# v6_config_io_16_17_21_22.net
KiCad netlist of a schematic drawn in Altium Designer
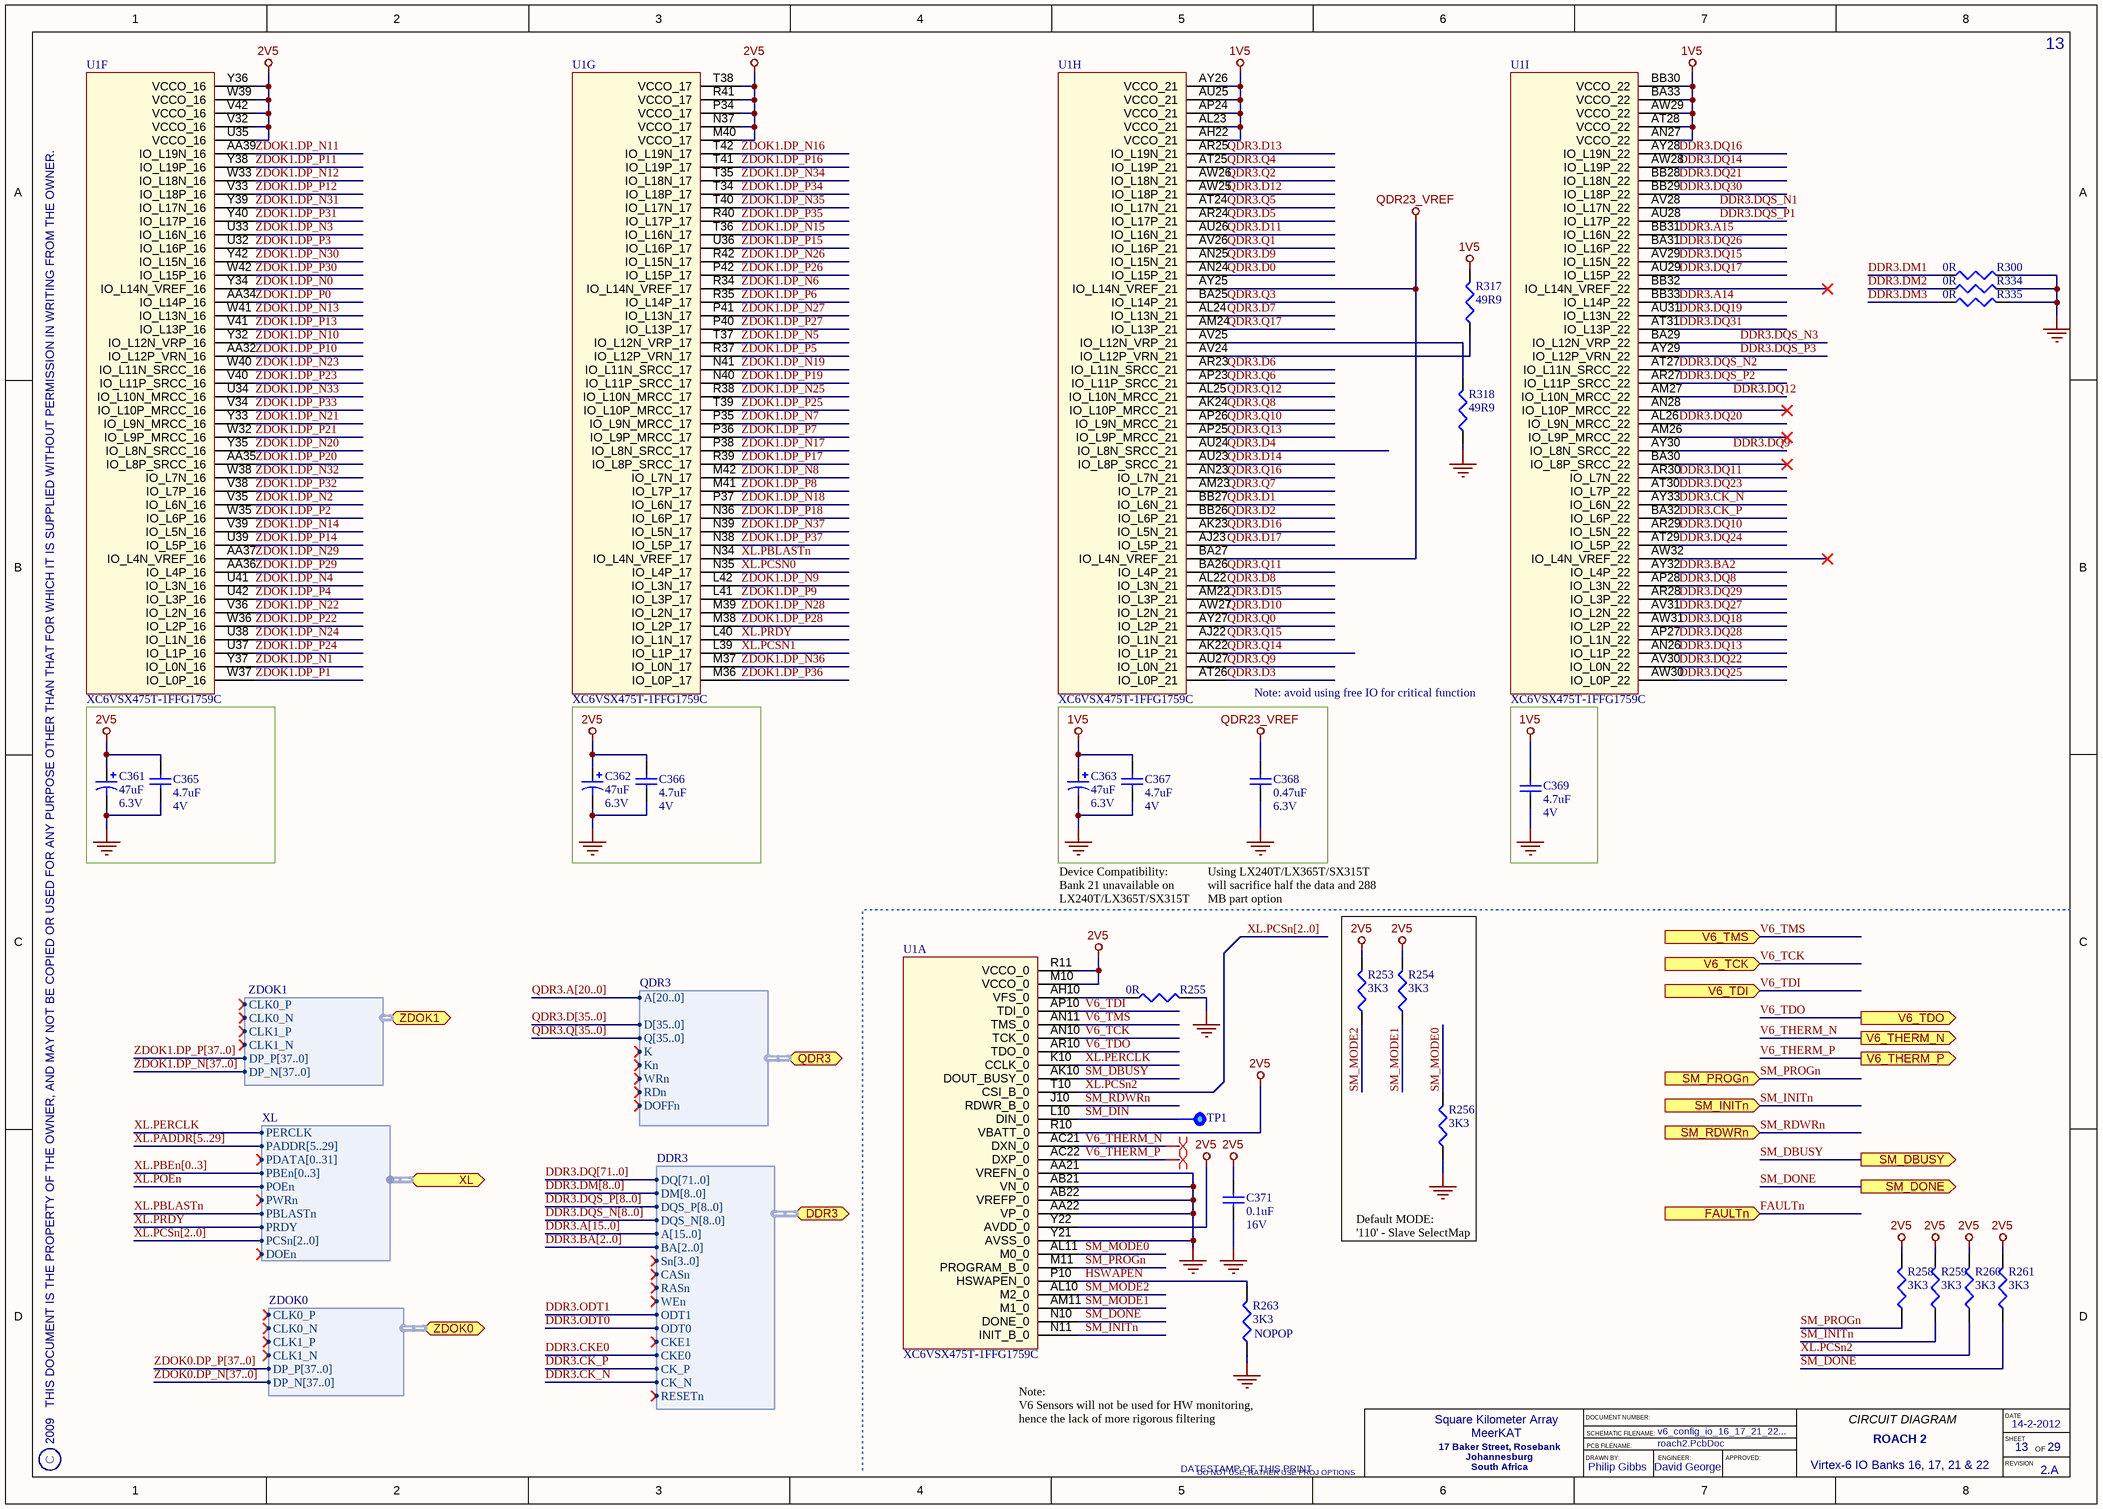
[diagram p0: v6_config_io_16_17_21_22.SchDoc]

(export (version "E")
  (design (tool "Eeschema 10.0.6"))
  (components
    (comp (ref "C361")
      (value "47uF")
      (footprint "CAPMP3528X120L")
      (description "47uF, Conductive Polymer Chip Capacitor")
      (fields
        (field (name "RATING") "6.3V")
        (field (name "MANUFACTURER") "KEMET")
        (field (name "PARTNUM") "T520T476M006ATE070")
      )
      (libsource (lib "altium_db") (part "CapPol"))
    )
    (comp (ref "C362")
      (value "47uF")
      (footprint "CAPMP3528X120L")
      (description "47uF, Conductive Polymer Chip Capacitor")
      (fields
        (field (name "RATING") "6.3V")
        (field (name "MANUFACTURER") "KEMET")
        (field (name "PARTNUM") "T520T476M006ATE070")
      )
      (libsource (lib "altium_db") (part "CapPol"))
    )
    (comp (ref "C363")
      (value "47uF")
      (footprint "CAPMP3528X120L")
      (description "47uF, Conductive Polymer Chip Capacitor")
      (fields
        (field (name "RATING") "6.3V")
        (field (name "MANUFACTURER") "KEMET")
        (field (name "PARTNUM") "T520T476M006ATE070")
      )
      (libsource (lib "altium_db") (part "CapPol"))
    )
    (comp (ref "C365")
      (value "4.7uF")
      (footprint "CAPC1005X60L")
      (description "4.7uF, Ceramic Capacitor")
      (fields
        (field (name "RATING") "4V")
        (field (name "MANUFACTURER") "MURATA")
        (field (name "PARTNUM") "AMK105BJ475MV-F")
      )
      (libsource (lib "altium_db") (part "CapStd"))
    )
    (comp (ref "C366")
      (value "4.7uF")
      (footprint "CAPC1005X60L")
      (description "4.7uF, Ceramic Capacitor")
      (fields
        (field (name "RATING") "4V")
        (field (name "MANUFACTURER") "MURATA")
        (field (name "PARTNUM") "AMK105BJ475MV-F")
      )
      (libsource (lib "altium_db") (part "CapStd"))
    )
    (comp (ref "C367")
      (value "4.7uF")
      (footprint "CAPC1005X60L")
      (description "4.7uF, Ceramic Capacitor")
      (fields
        (field (name "RATING") "4V")
        (field (name "MANUFACTURER") "MURATA")
        (field (name "PARTNUM") "AMK105BJ475MV-F")
      )
      (libsource (lib "altium_db") (part "CapStd"))
    )
    (comp (ref "C368")
      (value "0.47uF")
      (footprint "CAPC1005X55L")
      (description "0.47uF, Ceramic Capacitor")
      (fields
        (field (name "RATING") "6.3V")
        (field (name "MANUFACTURER") "MURATA")
        (field (name "PARTNUM") "GRM155R60J474KE19")
      )
      (libsource (lib "altium_db") (part "CapStd"))
    )
    (comp (ref "C369")
      (value "4.7uF")
      (footprint "CAPC1005X60L")
      (description "4.7uF, Ceramic Capacitor")
      (fields
        (field (name "RATING") "4V")
        (field (name "MANUFACTURER") "MURATA")
        (field (name "PARTNUM") "AMK105BJ475MV-F")
      )
      (libsource (lib "altium_db") (part "CapStd"))
    )
    (comp (ref "C371")
      (value "0.1uF")
      (footprint "CAPC1005X60L")
      (description "0.1uF, Ceramic Capacitor")
      (fields
        (field (name "RATING") "16V")
        (field (name "MANUFACTURER") "VENKEL")
        (field (name "PARTNUM") "C0402X7R160-104KN")
      )
      (libsource (lib "altium_db") (part "CapStd"))
    )
    (comp (ref "R253")
      (value "3K3")
      (footprint "RESC1005X40L")
      (description "3K3, 1.1mm x 0.5mm, Thick Film Resistor")
      (fields (field (name "MANUFACTURER") "ROYALOHM") (field (name "PARTNUM") "0402WGJ0332T1E"))
      (libsource (lib "altium_db") (part "ResStd"))
    )
    (comp (ref "R254")
      (value "3K3")
      (footprint "RESC1005X40L")
      (description "3K3, 1.1mm x 0.5mm, Thick Film Resistor")
      (fields (field (name "MANUFACTURER") "ROYALOHM") (field (name "PARTNUM") "0402WGJ0332T1E"))
      (libsource (lib "altium_db") (part "ResStd"))
    )
    (comp (ref "R255")
      (value "0R")
      (footprint "RESC1005X40L")
      (description "0R, 1.1mm x 0.5mm, Thick Film Resistor")
      (fields (field (name "MANUFACTURER") "ROYALOHM") (field (name "PARTNUM") "0402WG00000T1E"))
      (libsource (lib "altium_db") (part "ResStd"))
    )
    (comp (ref "R256")
      (value "3K3")
      (footprint "RESC1005X40L")
      (description "3K3, 1.1mm x 0.5mm, Thick Film Resistor")
      (fields (field (name "MANUFACTURER") "ROYALOHM") (field (name "PARTNUM") "0402WGJ0332T1E"))
      (libsource (lib "altium_db") (part "ResStd"))
    )
    (comp (ref "R258")
      (value "3K3")
      (footprint "RESC1005X40L")
      (description "3K3, 1.1mm x 0.5mm, Thick Film Resistor")
      (fields (field (name "MANUFACTURER") "ROYALOHM") (field (name "PARTNUM") "0402WGJ0332T1E"))
      (libsource (lib "altium_db") (part "ResStd"))
    )
    (comp (ref "R259")
      (value "3K3")
      (footprint "RESC1005X40L")
      (description "3K3, 1.1mm x 0.5mm, Thick Film Resistor")
      (fields (field (name "MANUFACTURER") "ROYALOHM") (field (name "PARTNUM") "0402WGJ0332T1E"))
      (libsource (lib "altium_db") (part "ResStd"))
    )
    (comp (ref "R260")
      (value "3K3")
      (footprint "RESC1005X40L")
      (description "3K3, 1.1mm x 0.5mm, Thick Film Resistor")
      (fields (field (name "MANUFACTURER") "ROYALOHM") (field (name "PARTNUM") "0402WGJ0332T1E"))
      (libsource (lib "altium_db") (part "ResStd"))
    )
    (comp (ref "R261")
      (value "3K3")
      (footprint "RESC1005X40L")
      (description "3K3, 1.1mm x 0.5mm, Thick Film Resistor")
      (fields (field (name "MANUFACTURER") "ROYALOHM") (field (name "PARTNUM") "0402WGJ0332T1E"))
      (libsource (lib "altium_db") (part "ResStd"))
    )
    (comp (ref "R263")
      (value "3K3")
      (footprint "RESC1005X40L")
      (description "3K3, 1.1mm x 0.5mm, Thick Film Resistor")
      (fields (field (name "MANUFACTURER") "ROYALOHM") (field (name "PARTNUM") "0402WGJ0332T1E"))
      (libsource (lib "altium_db") (part "ResStd"))
    )
    (comp (ref "R300")
      (value "0R")
      (footprint "RESC1005X40L")
      (description "0R, 1.1mm x 0.5mm, Thick Film Resistor")
      (fields (field (name "MANUFACTURER") "ROYALOHM") (field (name "PARTNUM") "0402WG00000T1E"))
      (libsource (lib "altium_db") (part "ResStd"))
    )
    (comp (ref "R317")
      (value "49R9")
      (footprint "RESC1005X40L")
      (description "49R9, 1.1mm x 0.5mm, Thick Film Resistor")
      (fields (field (name "MANUFACTURER") "ROYALOHM") (field (name "PARTNUM") "0402WGF499JT1E"))
      (libsource (lib "altium_db") (part "ResStd"))
    )
    (comp (ref "R318")
      (value "49R9")
      (footprint "RESC1005X40L")
      (description "49R9, 1.1mm x 0.5mm, Thick Film Resistor")
      (fields (field (name "MANUFACTURER") "ROYALOHM") (field (name "PARTNUM") "0402WGF499JT1E"))
      (libsource (lib "altium_db") (part "ResStd"))
    )
    (comp (ref "R334")
      (value "0R")
      (footprint "RESC1005X40L")
      (description "0R, 1.1mm x 0.5mm, Thick Film Resistor")
      (fields (field (name "MANUFACTURER") "ROYALOHM") (field (name "PARTNUM") "0402WG00000T1E"))
      (libsource (lib "altium_db") (part "ResStd"))
    )
    (comp (ref "R335")
      (value "0R")
      (footprint "RESC1005X40L")
      (description "0R, 1.1mm x 0.5mm, Thick Film Resistor")
      (fields (field (name "MANUFACTURER") "ROYALOHM") (field (name "PARTNUM") "0402WG00000T1E"))
      (libsource (lib "altium_db") (part "ResStd"))
    )
    (comp (ref "TP1")
      (value "Testpoint")
      (footprint "TP100")
      (description "1mm Diameter, through-hole, Circular Test-point")
      (libsource (lib "altium_db") (part "Testpoint"))
    )
    (comp (ref "U1")
      (value "XC6VSX475T-1FFG1759C")
      (footprint "FFG1759")
      (description "Virtex-6 475SXT 1760-pin FPGA")
      (fields (field (name "MANUFACTURER") "Xilinx"))
      (libsource (lib "altium_db") (part "XC6VSX475T-1FFG1759C"))
    )
  )
  (nets
    (net (code "161") (name "/DDR3.A14") (class "Default")
      (node (ref "U1") (pin "BB33") (pinfunction "IO_L14P_22_BB33") (pintype "passive"))
    )
    (net (code "162") (name "/DDR3.A15") (class "Default")
      (node (ref "U1") (pin "BB31") (pinfunction "IO_L16N_22_BB31") (pintype "passive"))
    )
    (net (code "164") (name "/DDR3.BA2") (class "Default")
      (node (ref "U1") (pin "AY32") (pinfunction "IO_L4P_22_AY32") (pintype "passive"))
    )
    (net (code "167") (name "/DDR3.CK_N") (class "Default")
      (node (ref "U1") (pin "AY33") (pinfunction "IO_L6N_22_AY33") (pintype "passive"))
    )
    (net (code "168") (name "/DDR3.CK_P") (class "Default")
      (node (ref "U1") (pin "BA32") (pinfunction "IO_L6P_22_BA32") (pintype "passive"))
    )
    (net (code "169") (name "/DDR3.DM1") (class "Default")
      (node (ref "R300") (pin "1") (pinfunction "1_1") (pintype "passive"))
    )
    (net (code "170") (name "/DDR3.DM2") (class "Default")
      (node (ref "R334") (pin "1") (pinfunction "1_1") (pintype "passive"))
    )
    (net (code "171") (name "/DDR3.DM3") (class "Default")
      (node (ref "R335") (pin "1") (pinfunction "1_1") (pintype "passive"))
    )
    (net (code "173") (name "/DDR3.DQ8") (class "Default")
      (node (ref "U1") (pin "AP28") (pinfunction "IO_L3N_22_AP28") (pintype "passive"))
    )
    (net (code "174") (name "/DDR3.DQ9") (class "Default")
      (node (ref "U1") (pin "AY30") (pinfunction "IO_L8N_SRCC_22_AY30") (pintype "passive"))
    )
    (net (code "175") (name "/DDR3.DQ10") (class "Default")
      (node (ref "U1") (pin "AR29") (pinfunction "IO_L5N_22_AR29") (pintype "passive"))
    )
    (net (code "176") (name "/DDR3.DQ11") (class "Default")
      (node (ref "U1") (pin "AR30") (pinfunction "IO_L7N_22_AR30") (pintype "passive"))
    )
    (net (code "177") (name "/DDR3.DQ12") (class "Default")
      (node (ref "U1") (pin "AM27") (pinfunction "IO_L10N_MRCC_22_AM27") (pintype "passive"))
    )
    (net (code "178") (name "/DDR3.DQ13") (class "Default")
      (node (ref "U1") (pin "AN26") (pinfunction "IO_L1P_22_AN26") (pintype "passive"))
    )
    (net (code "179") (name "/DDR3.DQ14") (class "Default")
      (node (ref "U1") (pin "AW28") (pinfunction "IO_L19P_22_AW28") (pintype "passive"))
    )
    (net (code "180") (name "/DDR3.DQ15") (class "Default")
      (node (ref "U1") (pin "AV29") (pinfunction "IO_L15N_22_AV29") (pintype "passive"))
    )
    (net (code "181") (name "/DDR3.DQ16") (class "Default")
      (node (ref "U1") (pin "AY28") (pinfunction "IO_L19N_22_AY28") (pintype "passive"))
    )
    (net (code "182") (name "/DDR3.DQ17") (class "Default")
      (node (ref "U1") (pin "AU29") (pinfunction "IO_L15P_22_AU29") (pintype "passive"))
    )
    (net (code "183") (name "/DDR3.DQ18") (class "Default")
      (node (ref "U1") (pin "AW31") (pinfunction "IO_L2P_22_AW31") (pintype "passive"))
    )
    (net (code "184") (name "/DDR3.DQ19") (class "Default")
      (node (ref "U1") (pin "AU31") (pinfunction "IO_L13N_22_AU31") (pintype "passive"))
    )
    (net (code "185") (name "/DDR3.DQ20") (class "Default")
      (node (ref "U1") (pin "AL26") (pinfunction "IO_L9N_MRCC_22_AL26") (pintype "passive"))
    )
    (net (code "186") (name "/DDR3.DQ21") (class "Default")
      (node (ref "U1") (pin "BB28") (pinfunction "IO_L18N_22_BB28") (pintype "passive"))
    )
    (net (code "187") (name "/DDR3.DQ22") (class "Default")
      (node (ref "U1") (pin "AV30") (pinfunction "IO_L0N_22_AV30") (pintype "passive"))
    )
    (net (code "188") (name "/DDR3.DQ23") (class "Default")
      (node (ref "U1") (pin "AT30") (pinfunction "IO_L7P_22_AT30") (pintype "passive"))
    )
    (net (code "189") (name "/DDR3.DQ24") (class "Default")
      (node (ref "U1") (pin "AT29") (pinfunction "IO_L5P_22_AT29") (pintype "passive"))
    )
    (net (code "190") (name "/DDR3.DQ25") (class "Default")
      (node (ref "U1") (pin "AW30") (pinfunction "IO_L0P_22_AW30") (pintype "passive"))
    )
    (net (code "191") (name "/DDR3.DQ26") (class "Default")
      (node (ref "U1") (pin "BA31") (pinfunction "IO_L16P_22_BA31") (pintype "passive"))
    )
    (net (code "192") (name "/DDR3.DQ27") (class "Default")
      (node (ref "U1") (pin "AV31") (pinfunction "IO_L2N_22_AV31") (pintype "passive"))
    )
    (net (code "193") (name "/DDR3.DQ28") (class "Default")
      (node (ref "U1") (pin "AP27") (pinfunction "IO_L1N_22_AP27") (pintype "passive"))
    )
    (net (code "194") (name "/DDR3.DQ29") (class "Default")
      (node (ref "U1") (pin "AR28") (pinfunction "IO_L3P_22_AR28") (pintype "passive"))
    )
    (net (code "195") (name "/DDR3.DQ30") (class "Default")
      (node (ref "U1") (pin "BB29") (pinfunction "IO_L18P_22_BB29") (pintype "passive"))
    )
    (net (code "196") (name "/DDR3.DQ31") (class "Default")
      (node (ref "U1") (pin "AT31") (pinfunction "IO_L13P_22_AT31") (pintype "passive"))
    )
    (net (code "197") (name "/DDR3.DQS_N1") (class "Default")
      (node (ref "U1") (pin "AV28") (pinfunction "IO_L17N_22_AV28") (pintype "passive"))
    )
    (net (code "198") (name "/DDR3.DQS_N2") (class "Default")
      (node (ref "U1") (pin "AT27") (pinfunction "IO_L11N_SRCC_22_AT27") (pintype "passive"))
    )
    (net (code "199") (name "/DDR3.DQS_N3") (class "Default")
      (node (ref "U1") (pin "BA29") (pinfunction "IO_L12N_VRP_22_BA29") (pintype "passive"))
    )
    (net (code "201") (name "/DDR3.DQS_P1") (class "Default")
      (node (ref "U1") (pin "AU28") (pinfunction "IO_L17P_22_AU28") (pintype "passive"))
    )
    (net (code "202") (name "/DDR3.DQS_P2") (class "Default")
      (node (ref "U1") (pin "AR27") (pinfunction "IO_L11P_SRCC_22_AR27") (pintype "passive"))
    )
    (net (code "203") (name "/DDR3.DQS_P3") (class "Default")
      (node (ref "U1") (pin "AY29") (pinfunction "IO_L12P_VRN_22_AY29") (pintype "passive"))
    )
    (net (code "209") (name "/HSWAPEN") (class "Default")
      (node (ref "R263") (pin "2") (pinfunction "2_2") (pintype "passive"))
      (node (ref "U1") (pin "P10") (pinfunction "HSWAPEN_0_P10") (pintype "passive"))
    )
    (net (code "211") (name "/QDR3.D0") (class "Default")
      (node (ref "U1") (pin "AN24") (pinfunction "IO_L15P_21_AN24") (pintype "passive"))
    )
    (net (code "212") (name "/QDR3.D1") (class "Default")
      (node (ref "U1") (pin "BB27") (pinfunction "IO_L6N_21_BB27") (pintype "passive"))
    )
    (net (code "213") (name "/QDR3.D2") (class "Default")
      (node (ref "U1") (pin "BB26") (pinfunction "IO_L6P_21_BB26") (pintype "passive"))
    )
    (net (code "214") (name "/QDR3.D3") (class "Default")
      (node (ref "U1") (pin "AT26") (pinfunction "IO_L0P_21_AT26") (pintype "passive"))
    )
    (net (code "215") (name "/QDR3.D4") (class "Default")
      (node (ref "U1") (pin "AU24") (pinfunction "IO_L8N_SRCC_21_AU24") (pintype "passive"))
    )
    (net (code "216") (name "/QDR3.D5") (class "Default")
      (node (ref "U1") (pin "AR24") (pinfunction "IO_L17P_21_AR24") (pintype "passive"))
    )
    (net (code "217") (name "/QDR3.D6") (class "Default")
      (node (ref "U1") (pin "AR23") (pinfunction "IO_L11N_SRCC_21_AR23") (pintype "passive"))
    )
    (net (code "218") (name "/QDR3.D7") (class "Default")
      (node (ref "U1") (pin "AL24") (pinfunction "IO_L13N_21_AL24") (pintype "passive"))
    )
    (net (code "219") (name "/QDR3.D8") (class "Default")
      (node (ref "U1") (pin "AL22") (pinfunction "IO_L3N_21_AL22") (pintype "passive"))
    )
    (net (code "220") (name "/QDR3.D9") (class "Default")
      (node (ref "U1") (pin "AN25") (pinfunction "IO_L15N_21_AN25") (pintype "passive"))
    )
    (net (code "221") (name "/QDR3.D10") (class "Default")
      (node (ref "U1") (pin "AW27") (pinfunction "IO_L2N_21_AW27") (pintype "passive"))
    )
    (net (code "222") (name "/QDR3.D11") (class "Default")
      (node (ref "U1") (pin "AU26") (pinfunction "IO_L16N_21_AU26") (pintype "passive"))
    )
    (net (code "223") (name "/QDR3.D12") (class "Default")
      (node (ref "U1") (pin "AW25") (pinfunction "IO_L18P_21_AW25") (pintype "passive"))
    )
    (net (code "224") (name "/QDR3.D13") (class "Default")
      (node (ref "U1") (pin "AR25") (pinfunction "IO_L19N_21_AR25") (pintype "passive"))
    )
    (net (code "225") (name "/QDR3.D14") (class "Default")
      (node (ref "U1") (pin "AU23") (pinfunction "IO_L8P_SRCC_21_AU23") (pintype "passive"))
    )
    (net (code "226") (name "/QDR3.D15") (class "Default")
      (node (ref "U1") (pin "AM22") (pinfunction "IO_L3P_21_AM22") (pintype "passive"))
    )
    (net (code "227") (name "/QDR3.D16") (class "Default")
      (node (ref "U1") (pin "AK23") (pinfunction "IO_L5N_21_AK23") (pintype "passive"))
    )
    (net (code "228") (name "/QDR3.D17") (class "Default")
      (node (ref "U1") (pin "AJ23") (pinfunction "IO_L5P_21_AJ23") (pintype "passive"))
    )
    (net (code "230") (name "/QDR3.Q0") (class "Default")
      (node (ref "U1") (pin "AY27") (pinfunction "IO_L2P_21_AY27") (pintype "passive"))
    )
    (net (code "231") (name "/QDR3.Q1") (class "Default")
      (node (ref "U1") (pin "AV26") (pinfunction "IO_L16P_21_AV26") (pintype "passive"))
    )
    (net (code "232") (name "/QDR3.Q2") (class "Default")
      (node (ref "U1") (pin "AW26") (pinfunction "IO_L18N_21_AW26") (pintype "passive"))
    )
    (net (code "233") (name "/QDR3.Q3") (class "Default")
      (node (ref "U1") (pin "BA25") (pinfunction "IO_L14P_21_BA25") (pintype "passive"))
    )
    (net (code "234") (name "/QDR3.Q4") (class "Default")
      (node (ref "U1") (pin "AT25") (pinfunction "IO_L19P_21_AT25") (pintype "passive"))
    )
    (net (code "235") (name "/QDR3.Q5") (class "Default")
      (node (ref "U1") (pin "AT24") (pinfunction "IO_L17N_21_AT24") (pintype "passive"))
    )
    (net (code "236") (name "/QDR3.Q6") (class "Default")
      (node (ref "U1") (pin "AP23") (pinfunction "IO_L11P_SRCC_21_AP23") (pintype "passive"))
    )
    (net (code "237") (name "/QDR3.Q7") (class "Default")
      (node (ref "U1") (pin "AM23") (pinfunction "IO_L7P_21_AM23") (pintype "passive"))
    )
    (net (code "238") (name "/QDR3.Q8") (class "Default")
      (node (ref "U1") (pin "AK24") (pinfunction "IO_L10P_MRCC_21_AK24") (pintype "passive"))
    )
    (net (code "239") (name "/QDR3.Q9") (class "Default")
      (node (ref "U1") (pin "AU27") (pinfunction "IO_L0N_21_AU27") (pintype "passive"))
    )
    (net (code "240") (name "/QDR3.Q10") (class "Default")
      (node (ref "U1") (pin "AP26") (pinfunction "IO_L9N_MRCC_21_AP26") (pintype "passive"))
    )
    (net (code "241") (name "/QDR3.Q11") (class "Default")
      (node (ref "U1") (pin "BA26") (pinfunction "IO_L4P_21_BA26") (pintype "passive"))
    )
    (net (code "242") (name "/QDR3.Q12") (class "Default")
      (node (ref "U1") (pin "AL25") (pinfunction "IO_L10N_MRCC_21_AL25") (pintype "passive"))
    )
    (net (code "243") (name "/QDR3.Q13") (class "Default")
      (node (ref "U1") (pin "AP25") (pinfunction "IO_L9P_MRCC_21_AP25") (pintype "passive"))
    )
    (net (code "244") (name "/QDR3.Q14") (class "Default")
      (node (ref "U1") (pin "AK22") (pinfunction "IO_L1P_21_AK22") (pintype "passive"))
    )
    (net (code "245") (name "/QDR3.Q15") (class "Default")
      (node (ref "U1") (pin "AJ22") (pinfunction "IO_L1N_21_AJ22") (pintype "passive"))
    )
    (net (code "246") (name "/QDR3.Q16") (class "Default")
      (node (ref "U1") (pin "AN23") (pinfunction "IO_L7N_21_AN23") (pintype "passive"))
    )
    (net (code "247") (name "/QDR3.Q17") (class "Default")
      (node (ref "U1") (pin "AM24") (pinfunction "IO_L13P_21_AM24") (pintype "passive"))
    )
    (net (code "249") (name "/SM_DBUSY") (class "Default")
      (node (ref "U1") (pin "AK10") (pinfunction "DOUT_BUSY_0_AK10") (pintype "passive"))
    )
    (net (code "250") (name "/SM_DIN") (class "Default")
      (node (ref "TP1") (pin "1") (pinfunction "1_1") (pintype "passive"))
      (node (ref "U1") (pin "L10") (pinfunction "DIN_0_L10") (pintype "passive"))
    )
    (net (code "251") (name "/SM_DONE") (class "Default")
      (node (ref "R261") (pin "1") (pinfunction "1_1") (pintype "passive"))
      (node (ref "U1") (pin "N10") (pinfunction "DONE_0_N10") (pintype "passive"))
    )
    (net (code "252") (name "/SM_INITn") (class "Default")
      (node (ref "R259") (pin "1") (pinfunction "1_1") (pintype "passive"))
      (node (ref "U1") (pin "N11") (pinfunction "INIT_B_0_N11") (pintype "passive"))
    )
    (net (code "253") (name "/SM_MODE0") (class "Default")
      (node (ref "R256") (pin "2") (pinfunction "2_2") (pintype "passive"))
      (node (ref "U1") (pin "AL11") (pinfunction "M0_0_AL11") (pintype "passive"))
    )
    (net (code "254") (name "/SM_MODE1") (class "Default")
      (node (ref "R254") (pin "1") (pinfunction "1_1") (pintype "passive"))
      (node (ref "U1") (pin "AM11") (pinfunction "M1_0_AM11") (pintype "passive"))
    )
    (net (code "255") (name "/SM_MODE2") (class "Default")
      (node (ref "R253") (pin "1") (pinfunction "1_1") (pintype "passive"))
      (node (ref "U1") (pin "AL10") (pinfunction "M2_0_AL10") (pintype "passive"))
    )
    (net (code "256") (name "/SM_PROGn") (class "Default")
      (node (ref "R258") (pin "1") (pinfunction "1_1") (pintype "passive"))
      (node (ref "U1") (pin "M11") (pinfunction "PROGRAM_B_0_M11") (pintype "passive"))
    )
    (net (code "257") (name "/SM_RDWRn") (class "Default")
      (node (ref "U1") (pin "J10") (pinfunction "RDWR_B_0_J10") (pintype "passive"))
    )
    (net (code "258") (name "/V6_TCK") (class "Default")
      (node (ref "U1") (pin "AN10") (pinfunction "TCK_0_AN10") (pintype "passive"))
    )
    (net (code "259") (name "/V6_TDI") (class "Default")
      (node (ref "U1") (pin "AP10") (pinfunction "TDI_0_AP10") (pintype "passive"))
    )
    (net (code "260") (name "/V6_TDO") (class "Default")
      (node (ref "U1") (pin "AR10") (pinfunction "TDO_0_AR10") (pintype "passive"))
    )
    (net (code "261") (name "/V6_THERM_N") (class "Default")
      (node (ref "U1") (pin "AC21") (pinfunction "DXN_0_AC21") (pintype "passive"))
    )
    (net (code "262") (name "/V6_THERM_P") (class "Default")
      (node (ref "U1") (pin "AC22") (pinfunction "DXP_0_AC22") (pintype "passive"))
    )
    (net (code "263") (name "/V6_TMS") (class "Default")
      (node (ref "U1") (pin "AN11") (pinfunction "TMS_0_AN11") (pintype "passive"))
    )
    (net (code "265") (name "/XL.PBLASTn") (class "Default")
      (node (ref "U1") (pin "N34") (pinfunction "IO_L4N_VREF_17_N34") (pintype "passive"))
    )
    (net (code "266") (name "/XL.PCSN0") (class "Default")
      (node (ref "U1") (pin "N35") (pinfunction "IO_L4P_17_N35") (pintype "passive"))
    )
    (net (code "267") (name "/XL.PCSN1") (class "Default")
      (node (ref "U1") (pin "L39") (pinfunction "IO_L1P_17_L39") (pintype "passive"))
    )
    (net (code "268") (name "/XL.PCSn2") (class "Default")
      (node (ref "R260") (pin "1") (pinfunction "1_1") (pintype "passive"))
      (node (ref "U1") (pin "T10") (pinfunction "CSI_B_0_T10") (pintype "passive"))
    )
    (net (code "270") (name "/XL.PERCLK") (class "Default")
      (node (ref "U1") (pin "K10") (pinfunction "CCLK_0_K10") (pintype "passive"))
    )
    (net (code "272") (name "/XL.PRDY") (class "Default")
      (node (ref "U1") (pin "L40") (pinfunction "IO_L1N_17_L40") (pintype "passive"))
    )
    (net (code "276") (name "/ZDOK1.DP_N0") (class "Default")
      (node (ref "U1") (pin "Y34") (pinfunction "IO_L14N_VREF_16_Y34") (pintype "passive"))
    )
    (net (code "277") (name "/ZDOK1.DP_N1") (class "Default")
      (node (ref "U1") (pin "Y37") (pinfunction "IO_L0N_16_Y37") (pintype "passive"))
    )
    (net (code "278") (name "/ZDOK1.DP_N2") (class "Default")
      (node (ref "U1") (pin "V35") (pinfunction "IO_L6N_16_V35") (pintype "passive"))
    )
    (net (code "279") (name "/ZDOK1.DP_N3") (class "Default")
      (node (ref "U1") (pin "U33") (pinfunction "IO_L16N_16_U33") (pintype "passive"))
    )
    (net (code "280") (name "/ZDOK1.DP_N4") (class "Default")
      (node (ref "U1") (pin "U41") (pinfunction "IO_L3N_16_U41") (pintype "passive"))
    )
    (net (code "281") (name "/ZDOK1.DP_N5") (class "Default")
      (node (ref "U1") (pin "T37") (pinfunction "IO_L12N_VRP_17_T37") (pintype "passive"))
    )
    (net (code "282") (name "/ZDOK1.DP_N6") (class "Default")
      (node (ref "U1") (pin "R34") (pinfunction "IO_L14N_VREF_17_R34") (pintype "passive"))
    )
    (net (code "283") (name "/ZDOK1.DP_N7") (class "Default")
      (node (ref "U1") (pin "P35") (pinfunction "IO_L9N_MRCC_17_P35") (pintype "passive"))
    )
    (net (code "284") (name "/ZDOK1.DP_N8") (class "Default")
      (node (ref "U1") (pin "M42") (pinfunction "IO_L7N_17_M42") (pintype "passive"))
    )
    (net (code "285") (name "/ZDOK1.DP_N9") (class "Default")
      (node (ref "U1") (pin "L42") (pinfunction "IO_L3N_17_L42") (pintype "passive"))
    )
    (net (code "286") (name "/ZDOK1.DP_N10") (class "Default")
      (node (ref "U1") (pin "Y32") (pinfunction "IO_L12N_VRP_16_Y32") (pintype "passive"))
    )
    (net (code "287") (name "/ZDOK1.DP_N11") (class "Default")
      (node (ref "U1") (pin "AA39") (pinfunction "IO_L19N_16_AA39") (pintype "passive"))
    )
    (net (code "288") (name "/ZDOK1.DP_N12") (class "Default")
      (node (ref "U1") (pin "W33") (pinfunction "IO_L18N_16_W33") (pintype "passive"))
    )
    (net (code "289") (name "/ZDOK1.DP_N13") (class "Default")
      (node (ref "U1") (pin "W41") (pinfunction "IO_L13N_16_W41") (pintype "passive"))
    )
    (net (code "290") (name "/ZDOK1.DP_N14") (class "Default")
      (node (ref "U1") (pin "V39") (pinfunction "IO_L5N_16_V39") (pintype "passive"))
    )
    (net (code "291") (name "/ZDOK1.DP_N15") (class "Default")
      (node (ref "U1") (pin "T36") (pinfunction "IO_L16N_17_T36") (pintype "passive"))
    )
    (net (code "292") (name "/ZDOK1.DP_N16") (class "Default")
      (node (ref "U1") (pin "T42") (pinfunction "IO_L19N_17_T42") (pintype "passive"))
    )
    (net (code "293") (name "/ZDOK1.DP_N17") (class "Default")
      (node (ref "U1") (pin "P38") (pinfunction "IO_L8N_SRCC_17_P38") (pintype "passive"))
    )
    (net (code "294") (name "/ZDOK1.DP_N18") (class "Default")
      (node (ref "U1") (pin "P37") (pinfunction "IO_L6N_17_P37") (pintype "passive"))
    )
    (net (code "295") (name "/ZDOK1.DP_N19") (class "Default")
      (node (ref "U1") (pin "N41") (pinfunction "IO_L11N_SRCC_17_N41") (pintype "passive"))
    )
    (net (code "296") (name "/ZDOK1.DP_N20") (class "Default")
      (node (ref "U1") (pin "Y35") (pinfunction "IO_L8N_SRCC_16_Y35") (pintype "passive"))
    )
    (net (code "297") (name "/ZDOK1.DP_N21") (class "Default")
      (node (ref "U1") (pin "Y33") (pinfunction "IO_L9N_MRCC_16_Y33") (pintype "passive"))
    )
    (net (code "298") (name "/ZDOK1.DP_N22") (class "Default")
      (node (ref "U1") (pin "V36") (pinfunction "IO_L2N_16_V36") (pintype "passive"))
    )
    (net (code "299") (name "/ZDOK1.DP_N23") (class "Default")
      (node (ref "U1") (pin "W40") (pinfunction "IO_L11N_SRCC_16_W40") (pintype "passive"))
    )
    (net (code "300") (name "/ZDOK1.DP_N24") (class "Default")
      (node (ref "U1") (pin "U38") (pinfunction "IO_L1N_16_U38") (pintype "passive"))
    )
    (net (code "301") (name "/ZDOK1.DP_N25") (class "Default")
      (node (ref "U1") (pin "R38") (pinfunction "IO_L10N_MRCC_17_R38") (pintype "passive"))
    )
    (net (code "302") (name "/ZDOK1.DP_N26") (class "Default")
      (node (ref "U1") (pin "R42") (pinfunction "IO_L15N_17_R42") (pintype "passive"))
    )
    (net (code "303") (name "/ZDOK1.DP_N27") (class "Default")
      (node (ref "U1") (pin "P41") (pinfunction "IO_L13N_17_P41") (pintype "passive"))
    )
    (net (code "304") (name "/ZDOK1.DP_N28") (class "Default")
      (node (ref "U1") (pin "M39") (pinfunction "IO_L2N_17_M39") (pintype "passive"))
    )
    (net (code "305") (name "/ZDOK1.DP_N29") (class "Default")
      (node (ref "U1") (pin "AA37") (pinfunction "IO_L4N_VREF_16_AA37") (pintype "passive"))
    )
    (net (code "306") (name "/ZDOK1.DP_N30") (class "Default")
      (node (ref "U1") (pin "Y42") (pinfunction "IO_L15N_16_Y42") (pintype "passive"))
    )
    (net (code "307") (name "/ZDOK1.DP_N31") (class "Default")
      (node (ref "U1") (pin "Y39") (pinfunction "IO_L17N_16_Y39") (pintype "passive"))
    )
    (net (code "308") (name "/ZDOK1.DP_N32") (class "Default")
      (node (ref "U1") (pin "W38") (pinfunction "IO_L7N_16_W38") (pintype "passive"))
    )
    (net (code "309") (name "/ZDOK1.DP_N33") (class "Default")
      (node (ref "U1") (pin "U34") (pinfunction "IO_L10N_MRCC_16_U34") (pintype "passive"))
    )
    (net (code "310") (name "/ZDOK1.DP_N34") (class "Default")
      (node (ref "U1") (pin "T35") (pinfunction "IO_L18N_17_T35") (pintype "passive"))
    )
    (net (code "311") (name "/ZDOK1.DP_N35") (class "Default")
      (node (ref "U1") (pin "T40") (pinfunction "IO_L17N_17_T40") (pintype "passive"))
    )
    (net (code "312") (name "/ZDOK1.DP_N36") (class "Default")
      (node (ref "U1") (pin "M37") (pinfunction "IO_L0N_17_M37") (pintype "passive"))
    )
    (net (code "313") (name "/ZDOK1.DP_N37") (class "Default")
      (node (ref "U1") (pin "N39") (pinfunction "IO_L5N_17_N39") (pintype "passive"))
    )
    (net (code "314") (name "/ZDOK1.DP_P0") (class "Default")
      (node (ref "U1") (pin "AA34") (pinfunction "IO_L14P_16_AA34") (pintype "passive"))
    )
    (net (code "315") (name "/ZDOK1.DP_P1") (class "Default")
      (node (ref "U1") (pin "W37") (pinfunction "IO_L0P_16_W37") (pintype "passive"))
    )
    (net (code "316") (name "/ZDOK1.DP_P2") (class "Default")
      (node (ref "U1") (pin "W35") (pinfunction "IO_L6P_16_W35") (pintype "passive"))
    )
    (net (code "317") (name "/ZDOK1.DP_P3") (class "Default")
      (node (ref "U1") (pin "U32") (pinfunction "IO_L16P_16_U32") (pintype "passive"))
    )
    (net (code "318") (name "/ZDOK1.DP_P4") (class "Default")
      (node (ref "U1") (pin "U42") (pinfunction "IO_L3P_16_U42") (pintype "passive"))
    )
    (net (code "319") (name "/ZDOK1.DP_P5") (class "Default")
      (node (ref "U1") (pin "R37") (pinfunction "IO_L12P_VRN_17_R37") (pintype "passive"))
    )
    (net (code "320") (name "/ZDOK1.DP_P6") (class "Default")
      (node (ref "U1") (pin "R35") (pinfunction "IO_L14P_17_R35") (pintype "passive"))
    )
    (net (code "321") (name "/ZDOK1.DP_P7") (class "Default")
      (node (ref "U1") (pin "P36") (pinfunction "IO_L9P_MRCC_17_P36") (pintype "passive"))
    )
    (net (code "322") (name "/ZDOK1.DP_P8") (class "Default")
      (node (ref "U1") (pin "M41") (pinfunction "IO_L7P_17_M41") (pintype "passive"))
    )
    (net (code "323") (name "/ZDOK1.DP_P9") (class "Default")
      (node (ref "U1") (pin "L41") (pinfunction "IO_L3P_17_L41") (pintype "passive"))
    )
    (net (code "324") (name "/ZDOK1.DP_P10") (class "Default")
      (node (ref "U1") (pin "AA32") (pinfunction "IO_L12P_VRN_16_AA32") (pintype "passive"))
    )
    (net (code "325") (name "/ZDOK1.DP_P11") (class "Default")
      (node (ref "U1") (pin "Y38") (pinfunction "IO_L19P_16_Y38") (pintype "passive"))
    )
    (net (code "326") (name "/ZDOK1.DP_P12") (class "Default")
      (node (ref "U1") (pin "V33") (pinfunction "IO_L18P_16_V33") (pintype "passive"))
    )
    (net (code "327") (name "/ZDOK1.DP_P13") (class "Default")
      (node (ref "U1") (pin "V41") (pinfunction "IO_L13P_16_V41") (pintype "passive"))
    )
    (net (code "328") (name "/ZDOK1.DP_P14") (class "Default")
      (node (ref "U1") (pin "U39") (pinfunction "IO_L5P_16_U39") (pintype "passive"))
    )
    (net (code "329") (name "/ZDOK1.DP_P15") (class "Default")
      (node (ref "U1") (pin "U36") (pinfunction "IO_L16P_17_U36") (pintype "passive"))
    )
    (net (code "330") (name "/ZDOK1.DP_P16") (class "Default")
      (node (ref "U1") (pin "T41") (pinfunction "IO_L19P_17_T41") (pintype "passive"))
    )
    (net (code "331") (name "/ZDOK1.DP_P17") (class "Default")
      (node (ref "U1") (pin "R39") (pinfunction "IO_L8P_SRCC_17_R39") (pintype "passive"))
    )
    (net (code "332") (name "/ZDOK1.DP_P18") (class "Default")
      (node (ref "U1") (pin "N36") (pinfunction "IO_L6P_17_N36") (pintype "passive"))
    )
    (net (code "333") (name "/ZDOK1.DP_P19") (class "Default")
      (node (ref "U1") (pin "N40") (pinfunction "IO_L11P_SRCC_17_N40") (pintype "passive"))
    )
    (net (code "334") (name "/ZDOK1.DP_P20") (class "Default")
      (node (ref "U1") (pin "AA35") (pinfunction "IO_L8P_SRCC_16_AA35") (pintype "passive"))
    )
    (net (code "335") (name "/ZDOK1.DP_P21") (class "Default")
      (node (ref "U1") (pin "W32") (pinfunction "IO_L9P_MRCC_16_W32") (pintype "passive"))
    )
    (net (code "336") (name "/ZDOK1.DP_P22") (class "Default")
      (node (ref "U1") (pin "W36") (pinfunction "IO_L2P_16_W36") (pintype "passive"))
    )
    (net (code "337") (name "/ZDOK1.DP_P23") (class "Default")
      (node (ref "U1") (pin "V40") (pinfunction "IO_L11P_SRCC_16_V40") (pintype "passive"))
    )
    (net (code "338") (name "/ZDOK1.DP_P24") (class "Default")
      (node (ref "U1") (pin "U37") (pinfunction "IO_L1P_16_U37") (pintype "passive"))
    )
    (net (code "339") (name "/ZDOK1.DP_P25") (class "Default")
      (node (ref "U1") (pin "T39") (pinfunction "IO_L10P_MRCC_17_T39") (pintype "passive"))
    )
    (net (code "340") (name "/ZDOK1.DP_P26") (class "Default")
      (node (ref "U1") (pin "P42") (pinfunction "IO_L15P_17_P42") (pintype "passive"))
    )
    (net (code "341") (name "/ZDOK1.DP_P27") (class "Default")
      (node (ref "U1") (pin "P40") (pinfunction "IO_L13P_17_P40") (pintype "passive"))
    )
    (net (code "342") (name "/ZDOK1.DP_P28") (class "Default")
      (node (ref "U1") (pin "M38") (pinfunction "IO_L2P_17_M38") (pintype "passive"))
    )
    (net (code "343") (name "/ZDOK1.DP_P29") (class "Default")
      (node (ref "U1") (pin "AA36") (pinfunction "IO_L4P_16_AA36") (pintype "passive"))
    )
    (net (code "344") (name "/ZDOK1.DP_P30") (class "Default")
      (node (ref "U1") (pin "W42") (pinfunction "IO_L15P_16_W42") (pintype "passive"))
    )
    (net (code "345") (name "/ZDOK1.DP_P31") (class "Default")
      (node (ref "U1") (pin "Y40") (pinfunction "IO_L17P_16_Y40") (pintype "passive"))
    )
    (net (code "346") (name "/ZDOK1.DP_P32") (class "Default")
      (node (ref "U1") (pin "V38") (pinfunction "IO_L7P_16_V38") (pintype "passive"))
    )
    (net (code "347") (name "/ZDOK1.DP_P33") (class "Default")
      (node (ref "U1") (pin "V34") (pinfunction "IO_L10P_MRCC_16_V34") (pintype "passive"))
    )
    (net (code "348") (name "/ZDOK1.DP_P34") (class "Default")
      (node (ref "U1") (pin "T34") (pinfunction "IO_L18P_17_T34") (pintype "passive"))
    )
    (net (code "349") (name "/ZDOK1.DP_P35") (class "Default")
      (node (ref "U1") (pin "R40") (pinfunction "IO_L17P_17_R40") (pintype "passive"))
    )
    (net (code "350") (name "/ZDOK1.DP_P36") (class "Default")
      (node (ref "U1") (pin "M36") (pinfunction "IO_L0P_17_M36") (pintype "passive"))
    )
    (net (code "351") (name "/ZDOK1.DP_P37") (class "Default")
      (node (ref "U1") (pin "N38") (pinfunction "IO_L5P_17_N38") (pintype "passive"))
    )
    (net (code "358") (name "1V5") (class "Default")
      (node (ref "C363") (pin "1") (pinfunction "1_1") (pintype "passive"))
      (node (ref "C367") (pin "2") (pinfunction "2_2") (pintype "passive"))
      (node (ref "C369") (pin "2") (pinfunction "2_2") (pintype "passive"))
      (node (ref "R317") (pin "2") (pinfunction "2_2") (pintype "passive"))
      (node (ref "U1") (pin "AH22") (pinfunction "VCCO_21_AH22") (pintype "passive"))
      (node (ref "U1") (pin "AL23") (pinfunction "VCCO_21_AL23") (pintype "passive"))
      (node (ref "U1") (pin "AN27") (pinfunction "VCCO_22_AN27") (pintype "passive"))
      (node (ref "U1") (pin "AP24") (pinfunction "VCCO_21_AP24") (pintype "passive"))
      (node (ref "U1") (pin "AT28") (pinfunction "VCCO_22_AT28") (pintype "passive"))
      (node (ref "U1") (pin "AU25") (pinfunction "VCCO_21_AU25") (pintype "passive"))
      (node (ref "U1") (pin "AW29") (pinfunction "VCCO_22_AW29") (pintype "passive"))
      (node (ref "U1") (pin "AY26") (pinfunction "VCCO_21_AY26") (pintype "passive"))
      (node (ref "U1") (pin "BA33") (pinfunction "VCCO_22_BA33") (pintype "passive"))
      (node (ref "U1") (pin "BB30") (pinfunction "VCCO_22_BB30") (pintype "passive"))
    )
    (net (code "359") (name "2V5") (class "Default")
      (node (ref "C361") (pin "1") (pinfunction "1_1") (pintype "passive"))
      (node (ref "C362") (pin "1") (pinfunction "1_1") (pintype "passive"))
      (node (ref "C365") (pin "2") (pinfunction "2_2") (pintype "passive"))
      (node (ref "C366") (pin "2") (pinfunction "2_2") (pintype "passive"))
      (node (ref "C371") (pin "2") (pinfunction "2_2") (pintype "passive"))
      (node (ref "R253") (pin "2") (pinfunction "2_2") (pintype "passive"))
      (node (ref "R254") (pin "2") (pinfunction "2_2") (pintype "passive"))
      (node (ref "R258") (pin "2") (pinfunction "2_2") (pintype "passive"))
      (node (ref "R259") (pin "2") (pinfunction "2_2") (pintype "passive"))
      (node (ref "R260") (pin "2") (pinfunction "2_2") (pintype "passive"))
      (node (ref "R261") (pin "2") (pinfunction "2_2") (pintype "passive"))
      (node (ref "U1") (pin "M10") (pinfunction "VCCO_0_M10") (pintype "passive"))
      (node (ref "U1") (pin "M40") (pinfunction "VCCO_17_M40") (pintype "passive"))
      (node (ref "U1") (pin "N37") (pinfunction "VCCO_17_N37") (pintype "passive"))
      (node (ref "U1") (pin "P34") (pinfunction "VCCO_17_P34") (pintype "passive"))
      (node (ref "U1") (pin "R10") (pinfunction "VBATT_0_R10") (pintype "passive"))
      (node (ref "U1") (pin "R11") (pinfunction "VCCO_0_R11") (pintype "passive"))
      (node (ref "U1") (pin "R41") (pinfunction "VCCO_17_R41") (pintype "passive"))
      (node (ref "U1") (pin "T38") (pinfunction "VCCO_17_T38") (pintype "passive"))
      (node (ref "U1") (pin "U35") (pinfunction "VCCO_16_U35") (pintype "passive"))
      (node (ref "U1") (pin "V32") (pinfunction "VCCO_16_V32") (pintype "passive"))
      (node (ref "U1") (pin "V42") (pinfunction "VCCO_16_V42") (pintype "passive"))
      (node (ref "U1") (pin "W39") (pinfunction "VCCO_16_W39") (pintype "passive"))
      (node (ref "U1") (pin "Y22") (pinfunction "AVDD_0_Y22") (pintype "passive"))
      (node (ref "U1") (pin "Y36") (pinfunction "VCCO_16_Y36") (pintype "passive"))
    )
    (net (code "360") (name "GND") (class "Default")
      (node (ref "C361") (pin "2") (pinfunction "2_2") (pintype "passive"))
      (node (ref "C362") (pin "2") (pinfunction "2_2") (pintype "passive"))
      (node (ref "C363") (pin "2") (pinfunction "2_2") (pintype "passive"))
      (node (ref "C365") (pin "1") (pinfunction "1_1") (pintype "passive"))
      (node (ref "C366") (pin "1") (pinfunction "1_1") (pintype "passive"))
      (node (ref "C367") (pin "1") (pinfunction "1_1") (pintype "passive"))
      (node (ref "C368") (pin "1") (pinfunction "1_1") (pintype "passive"))
      (node (ref "C369") (pin "1") (pinfunction "1_1") (pintype "passive"))
      (node (ref "C371") (pin "1") (pinfunction "1_1") (pintype "passive"))
      (node (ref "R255") (pin "2") (pinfunction "2_2") (pintype "passive"))
      (node (ref "R256") (pin "1") (pinfunction "1_1") (pintype "passive"))
      (node (ref "R263") (pin "1") (pinfunction "1_1") (pintype "passive"))
      (node (ref "R300") (pin "2") (pinfunction "2_2") (pintype "passive"))
      (node (ref "R318") (pin "1") (pinfunction "1_1") (pintype "passive"))
      (node (ref "R334") (pin "2") (pinfunction "2_2") (pintype "passive"))
      (node (ref "R335") (pin "2") (pinfunction "2_2") (pintype "passive"))
      (node (ref "U1") (pin "AA21") (pinfunction "VREFN_0_AA21") (pintype "passive"))
      (node (ref "U1") (pin "AA22") (pinfunction "VP_0_AA22") (pintype "passive"))
      (node (ref "U1") (pin "AB21") (pinfunction "VN_0_AB21") (pintype "passive"))
      (node (ref "U1") (pin "AB22") (pinfunction "VREFP_0_AB22") (pintype "passive"))
      (node (ref "U1") (pin "Y21") (pinfunction "AVSS_0_Y21") (pintype "passive"))
    )
    (net (code "361") (name "Net-(U1A-VFS_0)") (class "Default")
      (node (ref "R255") (pin "1") (pinfunction "1_1") (pintype "passive"))
      (node (ref "U1") (pin "AH10") (pinfunction "VFS_0_AH10") (pintype "passive"))
    )
    (net (code "362") (name "Net-(U1H-IO_L12N_VRP_21)") (class "Default")
      (node (ref "R318") (pin "2") (pinfunction "2_2") (pintype "passive"))
      (node (ref "U1") (pin "AV25") (pinfunction "IO_L12N_VRP_21_AV25") (pintype "passive"))
    )
    (net (code "363") (name "Net-(U1H-IO_L12P_VRN_21)") (class "Default")
      (node (ref "R317") (pin "1") (pinfunction "1_1") (pintype "passive"))
      (node (ref "U1") (pin "AV24") (pinfunction "IO_L12P_VRN_21_AV24") (pintype "passive"))
    )
    (net (code "364") (name "QDR23_VREF") (class "Default")
      (node (ref "C368") (pin "2") (pinfunction "2_2") (pintype "passive"))
      (node (ref "U1") (pin "AY25") (pinfunction "IO_L14N_VREF_21_AY25") (pintype "passive"))
      (node (ref "U1") (pin "BA27") (pinfunction "IO_L4N_VREF_21_BA27") (pintype "passive"))
    )
    (net (code "365") (name "unconnected-(U1I-IO_L4N_VREF_22-PadAW32)") (class "Default")
      (node (ref "U1") (pin "AW32") (pinfunction "IO_L4N_VREF_22_AW32") (pintype "passive+no_connect"))
    )
    (net (code "366") (name "unconnected-(U1I-IO_L8P_SRCC_22-PadBA30)") (class "Default")
      (node (ref "U1") (pin "BA30") (pinfunction "IO_L8P_SRCC_22_BA30") (pintype "passive+no_connect"))
    )
    (net (code "367") (name "unconnected-(U1I-IO_L9P_MRCC_22-PadAM26)") (class "Default")
      (node (ref "U1") (pin "AM26") (pinfunction "IO_L9P_MRCC_22_AM26") (pintype "passive+no_connect"))
    )
    (net (code "368") (name "unconnected-(U1I-IO_L10P_MRCC_22-PadAN28)") (class "Default")
      (node (ref "U1") (pin "AN28") (pinfunction "IO_L10P_MRCC_22_AN28") (pintype "passive+no_connect"))
    )
    (net (code "369") (name "unconnected-(U1I-IO_L14N_VREF_22-PadBB32)") (class "Default")
      (node (ref "U1") (pin "BB32") (pinfunction "IO_L14N_VREF_22_BB32") (pintype "passive+no_connect"))
    )
  )
)
